# 80PIN_FMU_REV_2A.net
KiCad netlist of a schematic drawn in Altium Designer
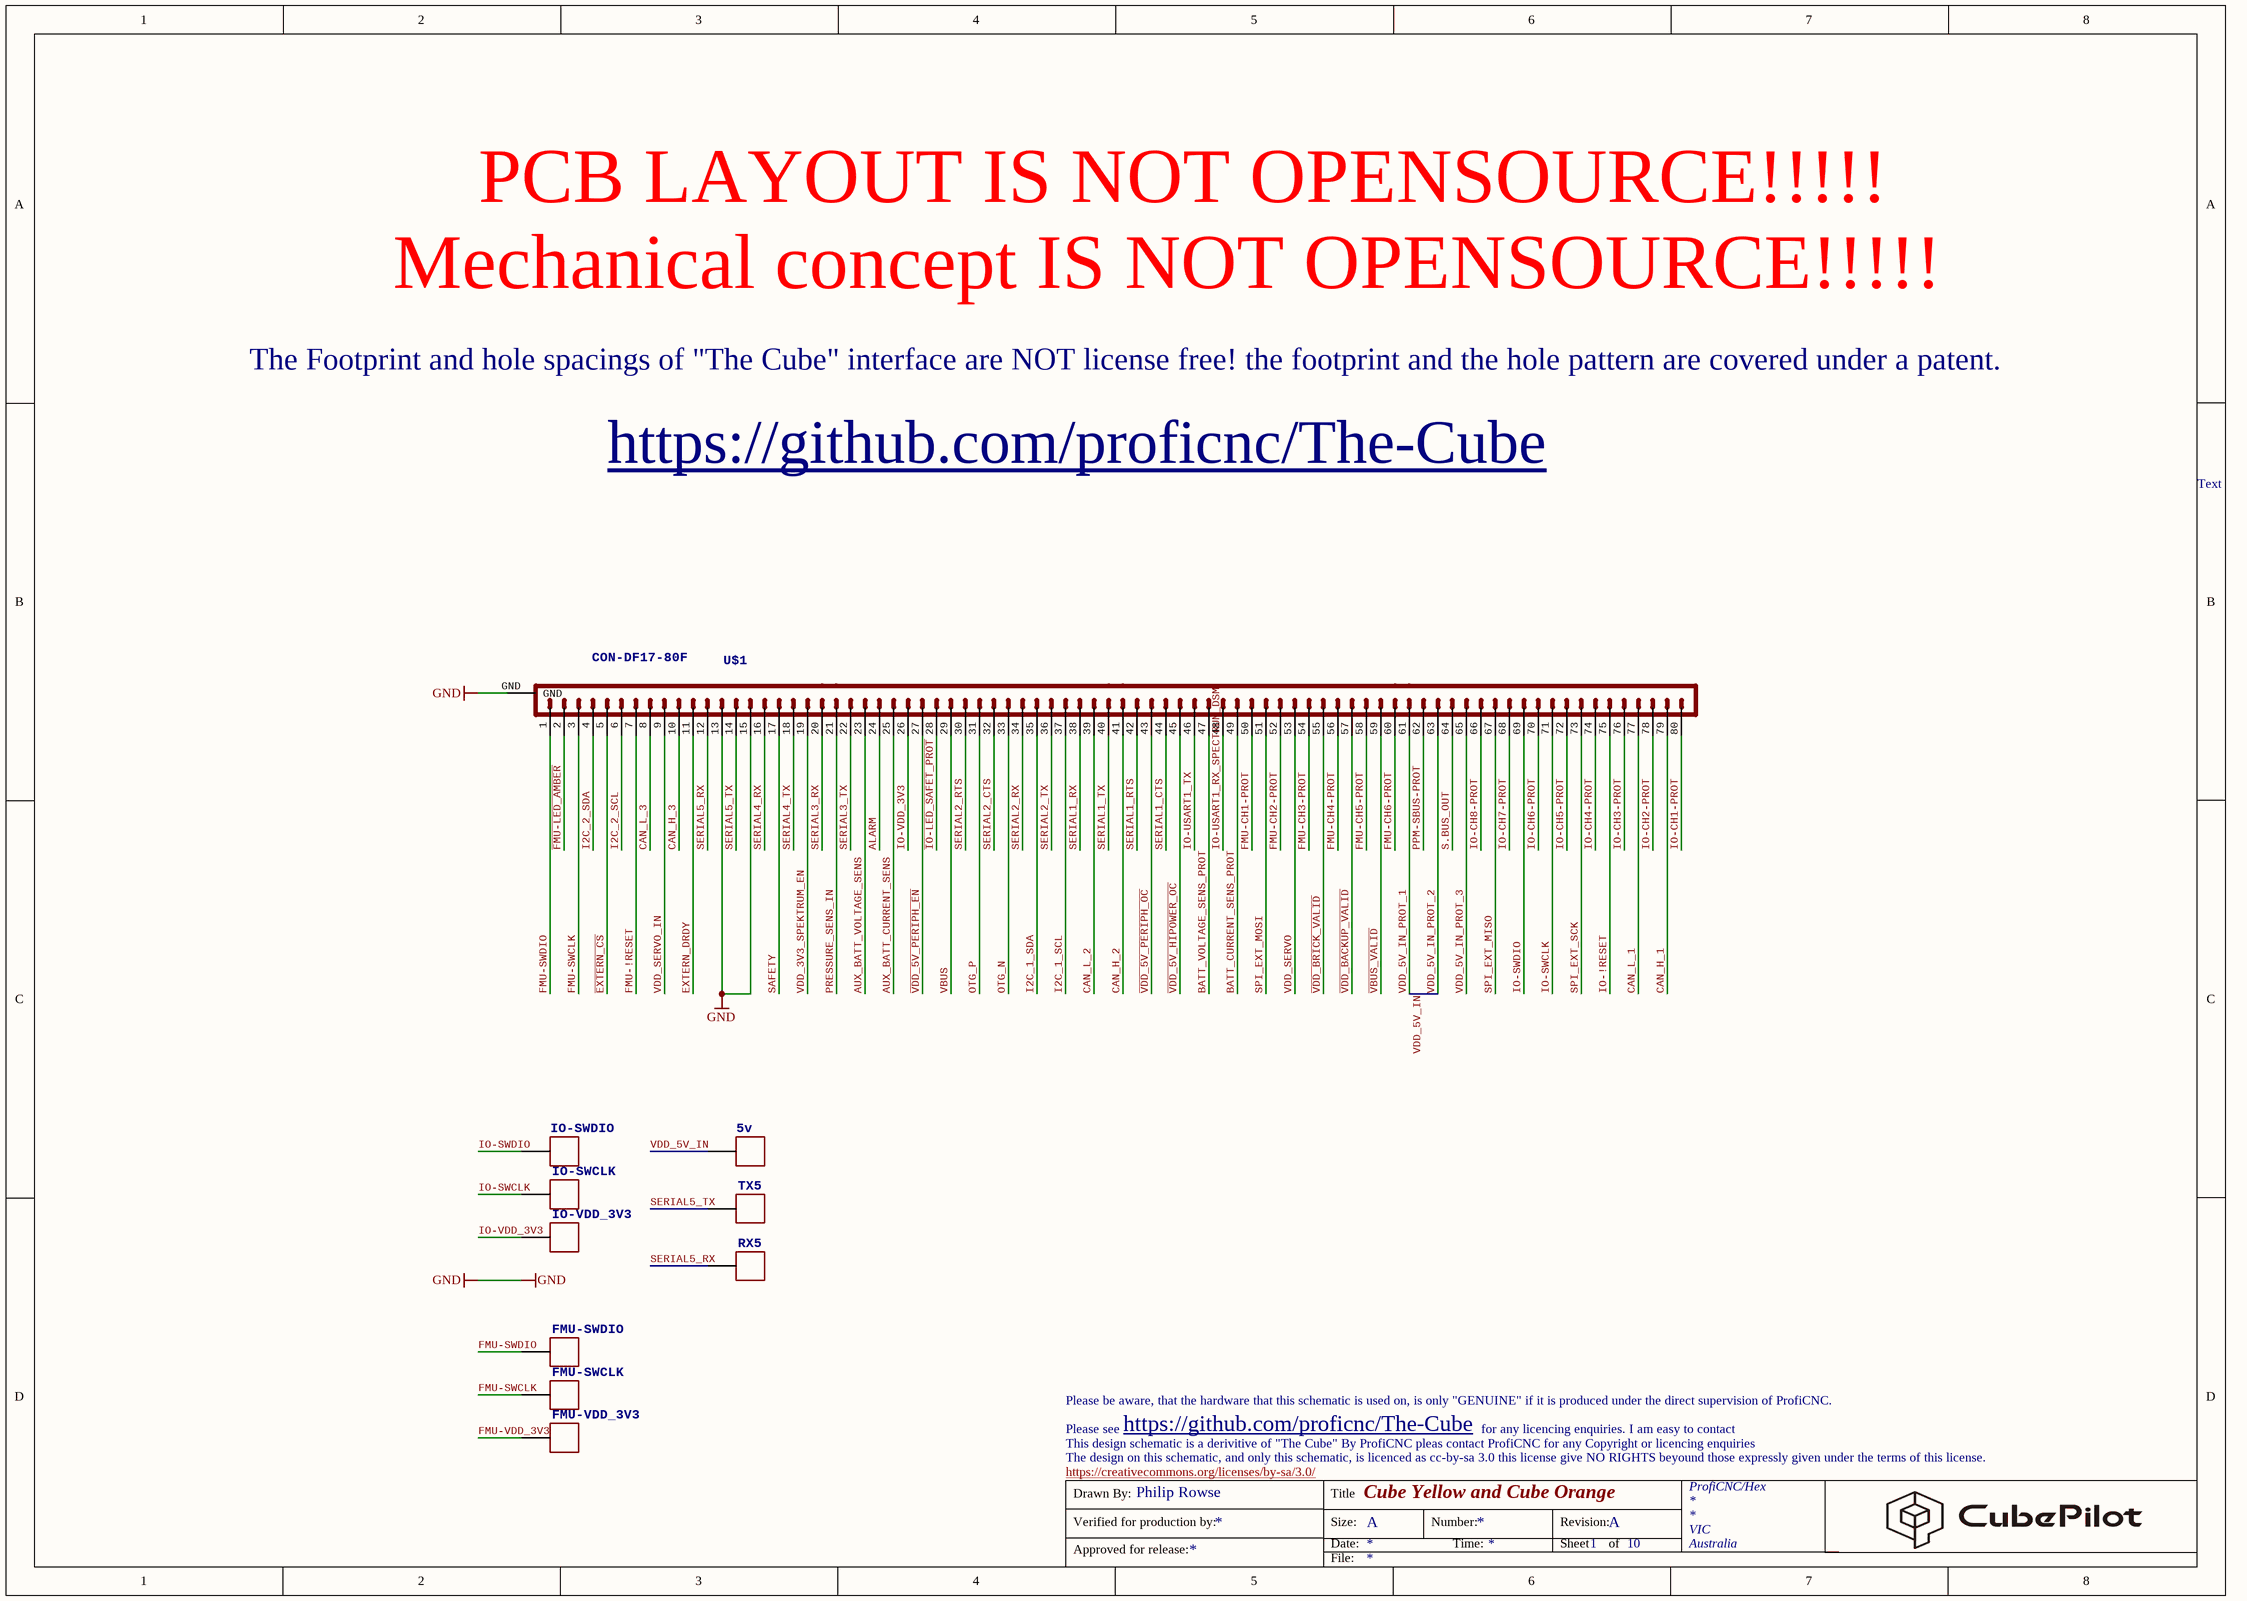
[diagram p0: 80PIN_FMU_REV_2A.SchDoc]

(export (version "E")
  (design (tool "Eeschema 10.0.6"))
  (components
    (comp (ref "5v") (value "PAD.04") (footprint "PAD.04X.04") (libsource (lib "pixhawk2") (part "PAD.04")))
    (comp (ref "FMU-SWCLK")
      (value "PAD.04")
      (footprint "PAD.04X.04")
      (libsource (lib "pixhawk2") (part "PAD.04"))
    )
    (comp (ref "FMU-SWDIO")
      (value "PAD.04")
      (footprint "PAD.04X.04")
      (libsource (lib "pixhawk2") (part "PAD.04"))
    )
    (comp (ref "FMU-VDD_3V3")
      (value "PAD.04")
      (footprint "PAD.04X.04")
      (libsource (lib "pixhawk2") (part "PAD.04"))
    )
    (comp (ref "IO-SWCLK")
      (value "PAD.04")
      (footprint "PAD.04X.04")
      (libsource (lib "pixhawk2") (part "PAD.04"))
    )
    (comp (ref "IO-SWDIO")
      (value "PAD.04")
      (footprint "PAD.04X.04")
      (libsource (lib "pixhawk2") (part "PAD.04"))
    )
    (comp (ref "IO-VDD_3V3")
      (value "PAD.04")
      (footprint "PAD.04X.04")
      (libsource (lib "pixhawk2") (part "PAD.04"))
    )
    (comp (ref "RX5") (value "PAD.04") (footprint "PAD.04X.04") (libsource (lib "pixhawk2") (part "PAD.04")))
    (comp (ref "TX5") (value "PAD.04") (footprint "PAD.04X.04") (libsource (lib "pixhawk2") (part "PAD.04")))
    (comp (ref "U$1")
      (value "CON-DF17-80F")
      (footprint "CON-DF17-80F")
      (description "CONN RECEPT 80POS .5MM SMD W/FIT")
      (libsource (lib "pixhawk2") (part "CON-DF17-80F"))
    )
  )
  (nets
    (net (code "1") (name "/ALARM") (class "Default")
      (node (ref "U$1") (pin "24") (pinfunction "24_24") (pintype "passive"))
    )
    (net (code "2") (name "/AUX_BATT_CURRENT_SENS") (class "Default")
      (node (ref "U$1") (pin "25") (pinfunction "25_25") (pintype "passive"))
    )
    (net (code "3") (name "/AUX_BATT_VOLTAGE_SENS") (class "Default")
      (node (ref "U$1") (pin "23") (pinfunction "23_23") (pintype "passive"))
    )
    (net (code "4") (name "/BATT_CURRENT_SENS_PROT") (class "Default")
      (node (ref "U$1") (pin "49") (pinfunction "49_49") (pintype "passive"))
    )
    (net (code "5") (name "/BATT_VOLTAGE_SENS_PROT") (class "Default")
      (node (ref "U$1") (pin "47") (pinfunction "47_47") (pintype "passive"))
    )
    (net (code "6") (name "/CAN_H_1") (class "Default")
      (node (ref "U$1") (pin "79") (pinfunction "79_79") (pintype "passive"))
    )
    (net (code "7") (name "/CAN_H_2") (class "Default")
      (node (ref "U$1") (pin "41") (pinfunction "41_41") (pintype "passive"))
    )
    (net (code "8") (name "/CAN_H_3") (class "Default")
      (node (ref "U$1") (pin "10") (pinfunction "10_10") (pintype "passive"))
    )
    (net (code "9") (name "/CAN_L_1") (class "Default")
      (node (ref "U$1") (pin "77") (pinfunction "77_77") (pintype "passive"))
    )
    (net (code "10") (name "/CAN_L_2") (class "Default")
      (node (ref "U$1") (pin "39") (pinfunction "39_39") (pintype "passive"))
    )
    (net (code "11") (name "/CAN_L_3") (class "Default")
      (node (ref "U$1") (pin "8") (pinfunction "8_8") (pintype "passive"))
    )
    (net (code "12") (name "/EXTERN_DRDY") (class "Default")
      (node (ref "U$1") (pin "11") (pinfunction "11_11") (pintype "passive"))
    )
    (net (code "13") (name "/FMU-!RESET") (class "Default")
      (node (ref "U$1") (pin "7") (pinfunction "7_7") (pintype "passive"))
    )
    (net (code "14") (name "/FMU-CH1-PROT") (class "Default")
      (node (ref "U$1") (pin "50") (pinfunction "50_50") (pintype "passive"))
    )
    (net (code "15") (name "/FMU-CH2-PROT") (class "Default")
      (node (ref "U$1") (pin "52") (pinfunction "52_52") (pintype "passive"))
    )
    (net (code "16") (name "/FMU-CH3-PROT") (class "Default")
      (node (ref "U$1") (pin "54") (pinfunction "54_54") (pintype "passive"))
    )
    (net (code "17") (name "/FMU-CH4-PROT") (class "Default")
      (node (ref "U$1") (pin "56") (pinfunction "56_56") (pintype "passive"))
    )
    (net (code "18") (name "/FMU-CH5-PROT") (class "Default")
      (node (ref "U$1") (pin "58") (pinfunction "58_58") (pintype "passive"))
    )
    (net (code "19") (name "/FMU-CH6-PROT") (class "Default")
      (node (ref "U$1") (pin "60") (pinfunction "60_60") (pintype "passive"))
    )
    (net (code "20") (name "/FMU-SWCLK") (class "Default")
      (node (ref "FMU-SWCLK") (pin "P$1") (pinfunction "P$1_P$1") (pintype "passive"))
      (node (ref "U$1") (pin "3") (pinfunction "3_3") (pintype "passive"))
    )
    (net (code "21") (name "/FMU-SWDIO") (class "Default")
      (node (ref "FMU-SWDIO") (pin "P$1") (pinfunction "P$1_P$1") (pintype "passive"))
      (node (ref "U$1") (pin "1") (pinfunction "1_1") (pintype "passive"))
    )
    (net (code "22") (name "/FMU-VDD_3V3") (class "Default")
      (node (ref "FMU-VDD_3V3") (pin "P$1") (pinfunction "P$1_P$1") (pintype "passive"))
    )
    (net (code "23") (name "/I2C_1_SCL") (class "Default")
      (node (ref "U$1") (pin "37") (pinfunction "37_37") (pintype "passive"))
    )
    (net (code "24") (name "/I2C_1_SDA") (class "Default")
      (node (ref "U$1") (pin "35") (pinfunction "35_35") (pintype "passive"))
    )
    (net (code "25") (name "/I2C_2_SCL") (class "Default")
      (node (ref "U$1") (pin "6") (pinfunction "6_6") (pintype "passive"))
    )
    (net (code "26") (name "/I2C_2_SDA") (class "Default")
      (node (ref "U$1") (pin "4") (pinfunction "4_4") (pintype "passive"))
    )
    (net (code "27") (name "/IO-!RESET") (class "Default")
      (node (ref "U$1") (pin "75") (pinfunction "75_75") (pintype "passive"))
    )
    (net (code "28") (name "/IO-CH1-PROT") (class "Default")
      (node (ref "U$1") (pin "80") (pinfunction "80_80") (pintype "passive"))
    )
    (net (code "29") (name "/IO-CH2-PROT") (class "Default")
      (node (ref "U$1") (pin "78") (pinfunction "78_78") (pintype "passive"))
    )
    (net (code "30") (name "/IO-CH3-PROT") (class "Default")
      (node (ref "U$1") (pin "76") (pinfunction "76_76") (pintype "passive"))
    )
    (net (code "31") (name "/IO-CH4-PROT") (class "Default")
      (node (ref "U$1") (pin "74") (pinfunction "74_74") (pintype "passive"))
    )
    (net (code "32") (name "/IO-CH5-PROT") (class "Default")
      (node (ref "U$1") (pin "72") (pinfunction "72_72") (pintype "passive"))
    )
    (net (code "33") (name "/IO-CH6-PROT") (class "Default")
      (node (ref "U$1") (pin "70") (pinfunction "70_70") (pintype "passive"))
    )
    (net (code "34") (name "/IO-CH7-PROT") (class "Default")
      (node (ref "U$1") (pin "68") (pinfunction "68_68") (pintype "passive"))
    )
    (net (code "35") (name "/IO-CH8-PROT") (class "Default")
      (node (ref "U$1") (pin "66") (pinfunction "66_66") (pintype "passive"))
    )
    (net (code "36") (name "/IO-SWCLK") (class "Default")
      (node (ref "IO-SWCLK") (pin "P$1") (pinfunction "P$1_P$1") (pintype "passive"))
      (node (ref "U$1") (pin "71") (pinfunction "71_71") (pintype "passive"))
    )
    (net (code "37") (name "/IO-SWDIO") (class "Default")
      (node (ref "IO-SWDIO") (pin "P$1") (pinfunction "P$1_P$1") (pintype "passive"))
      (node (ref "U$1") (pin "69") (pinfunction "69_69") (pintype "passive"))
    )
    (net (code "38") (name "/IO-USART1_RX_SPECTRUM_DSM") (class "Default")
      (node (ref "U$1") (pin "48") (pinfunction "48_48") (pintype "passive"))
    )
    (net (code "39") (name "/IO-USART1_TX") (class "Default")
      (node (ref "U$1") (pin "46") (pinfunction "46_46") (pintype "passive"))
    )
    (net (code "40") (name "/IO-VDD_3V3") (class "Default")
      (node (ref "IO-VDD_3V3") (pin "P$1") (pinfunction "P$1_P$1") (pintype "passive"))
      (node (ref "U$1") (pin "26") (pinfunction "26_26") (pintype "passive"))
    )
    (net (code "41") (name "/OTG_N") (class "Default")
      (node (ref "U$1") (pin "33") (pinfunction "33_33") (pintype "passive"))
    )
    (net (code "42") (name "/OTG_P") (class "Default")
      (node (ref "U$1") (pin "31") (pinfunction "31_31") (pintype "passive"))
    )
    (net (code "43") (name "/PPM-SBUS-PROT") (class "Default")
      (node (ref "U$1") (pin "62") (pinfunction "62_62") (pintype "passive"))
    )
    (net (code "44") (name "/PRESSURE_SENS_IN") (class "Default")
      (node (ref "U$1") (pin "21") (pinfunction "21_21") (pintype "passive"))
    )
    (net (code "45") (name "/S.BUS_OUT") (class "Default")
      (node (ref "U$1") (pin "64") (pinfunction "64_64") (pintype "passive"))
    )
    (net (code "46") (name "/SAFETY") (class "Default")
      (node (ref "U$1") (pin "17") (pinfunction "17_17") (pintype "passive"))
    )
    (net (code "47") (name "/SERIAL1_CTS") (class "Default")
      (node (ref "U$1") (pin "44") (pinfunction "44_44") (pintype "passive"))
    )
    (net (code "48") (name "/SERIAL1_RTS") (class "Default")
      (node (ref "U$1") (pin "42") (pinfunction "42_42") (pintype "passive"))
    )
    (net (code "49") (name "/SERIAL1_RX") (class "Default")
      (node (ref "U$1") (pin "38") (pinfunction "38_38") (pintype "passive"))
    )
    (net (code "50") (name "/SERIAL1_TX") (class "Default")
      (node (ref "U$1") (pin "40") (pinfunction "40_40") (pintype "passive"))
    )
    (net (code "51") (name "/SERIAL2_CTS") (class "Default")
      (node (ref "U$1") (pin "32") (pinfunction "32_32") (pintype "passive"))
    )
    (net (code "52") (name "/SERIAL2_RTS") (class "Default")
      (node (ref "U$1") (pin "30") (pinfunction "30_30") (pintype "passive"))
    )
    (net (code "53") (name "/SERIAL2_RX") (class "Default")
      (node (ref "U$1") (pin "34") (pinfunction "34_34") (pintype "passive"))
    )
    (net (code "54") (name "/SERIAL2_TX") (class "Default")
      (node (ref "U$1") (pin "36") (pinfunction "36_36") (pintype "passive"))
    )
    (net (code "55") (name "/SERIAL3_RX") (class "Default")
      (node (ref "U$1") (pin "20") (pinfunction "20_20") (pintype "passive"))
    )
    (net (code "56") (name "/SERIAL3_TX") (class "Default")
      (node (ref "U$1") (pin "22") (pinfunction "22_22") (pintype "passive"))
    )
    (net (code "57") (name "/SERIAL4_RX") (class "Default")
      (node (ref "U$1") (pin "16") (pinfunction "16_16") (pintype "passive"))
    )
    (net (code "58") (name "/SERIAL4_TX") (class "Default")
      (node (ref "U$1") (pin "18") (pinfunction "18_18") (pintype "passive"))
    )
    (net (code "59") (name "/SERIAL5_RX") (class "Default")
      (node (ref "RX5") (pin "P$1") (pinfunction "P$1_P$1") (pintype "passive"))
      (node (ref "U$1") (pin "12") (pinfunction "12_12") (pintype "passive"))
    )
    (net (code "60") (name "/SERIAL5_TX") (class "Default")
      (node (ref "TX5") (pin "P$1") (pinfunction "P$1_P$1") (pintype "passive"))
      (node (ref "U$1") (pin "14") (pinfunction "14_14") (pintype "passive"))
    )
    (net (code "61") (name "/SPI_EXT_MISO") (class "Default")
      (node (ref "U$1") (pin "67") (pinfunction "67_67") (pintype "passive"))
    )
    (net (code "62") (name "/SPI_EXT_MOSI") (class "Default")
      (node (ref "U$1") (pin "51") (pinfunction "51_51") (pintype "passive"))
    )
    (net (code "63") (name "/SPI_EXT_SCK") (class "Default")
      (node (ref "U$1") (pin "73") (pinfunction "73_73") (pintype "passive"))
    )
    (net (code "64") (name "/VBUS") (class "Default")
      (node (ref "U$1") (pin "29") (pinfunction "29_29") (pintype "passive"))
    )
    (net (code "65") (name "/VDD_3V3_SPEKTRUM_EN") (class "Default")
      (node (ref "U$1") (pin "19") (pinfunction "19_19") (pintype "passive"))
    )
    (net (code "66") (name "/VDD_5V_IN") (class "Default")
      (node (ref "5v") (pin "P$1") (pinfunction "P$1_P$1") (pintype "passive"))
      (node (ref "U$1") (pin "61") (pinfunction "61_61") (pintype "passive"))
      (node (ref "U$1") (pin "63") (pinfunction "63_63") (pintype "passive"))
    )
    (net (code "67") (name "/VDD_5V_IN_PROT_3") (class "Default")
      (node (ref "U$1") (pin "65") (pinfunction "65_65") (pintype "passive"))
    )
    (net (code "68") (name "/VDD_SERVO") (class "Default")
      (node (ref "U$1") (pin "53") (pinfunction "53_53") (pintype "passive"))
    )
    (net (code "69") (name "/VDD_SERVO_IN") (class "Default")
      (node (ref "U$1") (pin "9") (pinfunction "9_9") (pintype "passive"))
    )
    (net (code "70") (name "/~{EXTERN_CS}") (class "Default")
      (node (ref "U$1") (pin "5") (pinfunction "5_5") (pintype "passive"))
    )
    (net (code "71") (name "/~{FMU-LED_AMBER}") (class "Default")
      (node (ref "U$1") (pin "2") (pinfunction "2_2") (pintype "passive"))
    )
    (net (code "72") (name "/~{IO-LED_SAFET_PROT}") (class "Default")
      (node (ref "U$1") (pin "28") (pinfunction "28_28") (pintype "passive"))
    )
    (net (code "73") (name "/~{VBUS_VALID}") (class "Default")
      (node (ref "U$1") (pin "59") (pinfunction "59_59") (pintype "passive"))
    )
    (net (code "74") (name "/~{VDD_5V_HIPOWER_OC}") (class "Default")
      (node (ref "U$1") (pin "45") (pinfunction "45_45") (pintype "passive"))
    )
    (net (code "75") (name "/~{VDD_5V_PERIPH_EN}") (class "Default")
      (node (ref "U$1") (pin "27") (pinfunction "27_27") (pintype "passive"))
    )
    (net (code "76") (name "/~{VDD_5V_PERIPH_OC}") (class "Default")
      (node (ref "U$1") (pin "43") (pinfunction "43_43") (pintype "passive"))
    )
    (net (code "77") (name "/~{VDD_BACKUP_VALID}") (class "Default")
      (node (ref "U$1") (pin "57") (pinfunction "57_57") (pintype "passive"))
    )
    (net (code "78") (name "/~{VDD_BRICK_VALID}") (class "Default")
      (node (ref "U$1") (pin "55") (pinfunction "55_55") (pintype "passive"))
    )
    (net (code "79") (name "GND") (class "Default")
      (node (ref "U$1") (pin "13") (pinfunction "13_13") (pintype "passive"))
      (node (ref "U$1") (pin "15") (pinfunction "15_15") (pintype "passive"))
      (node (ref "U$1") (pin "GND") (pinfunction "GND_GND") (pintype "passive"))
    )
  )
)
